# calculator6.net
KiCad netlist of a schematic drawn in EAGLE
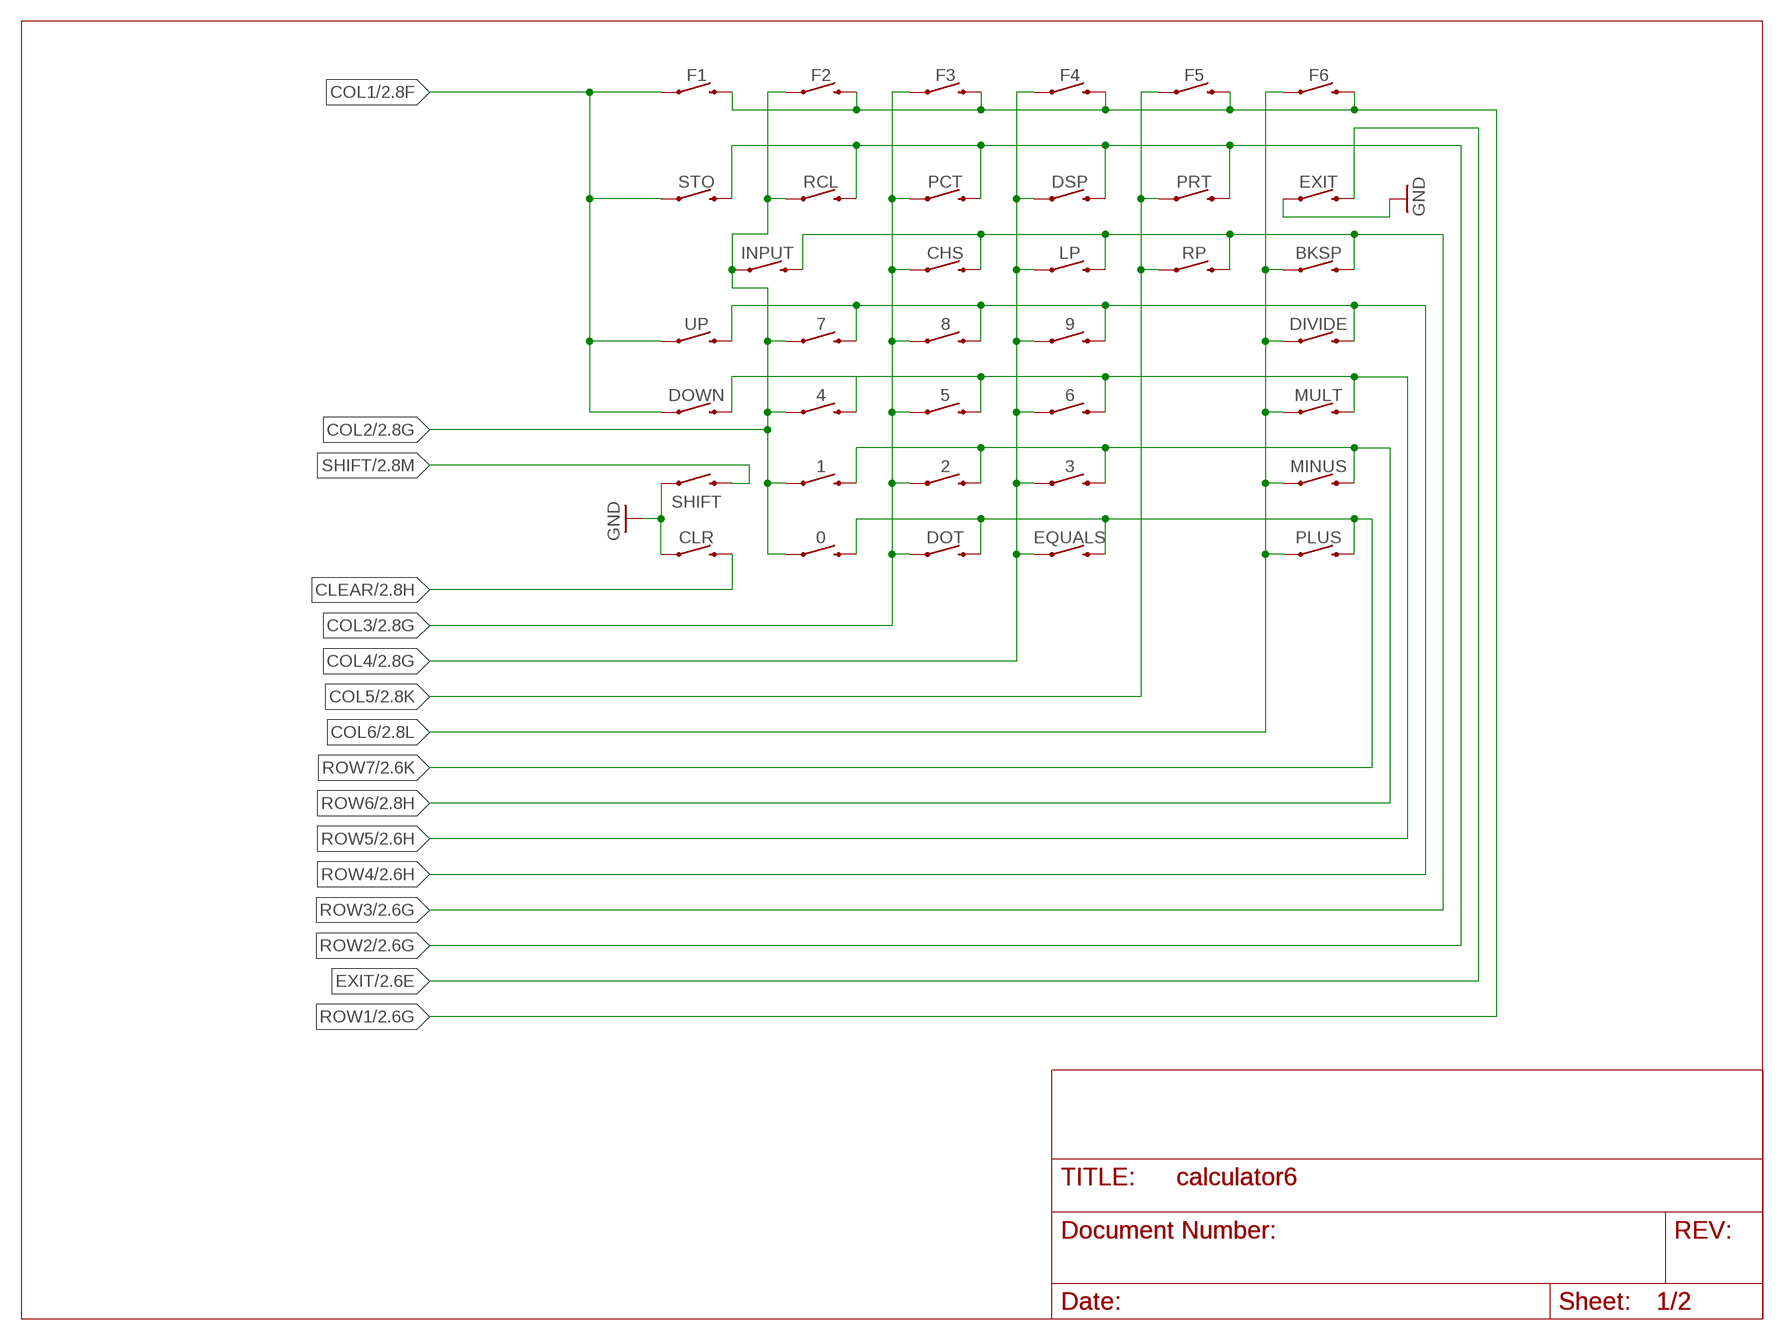
[diagram p0: schematic, sheet 1]
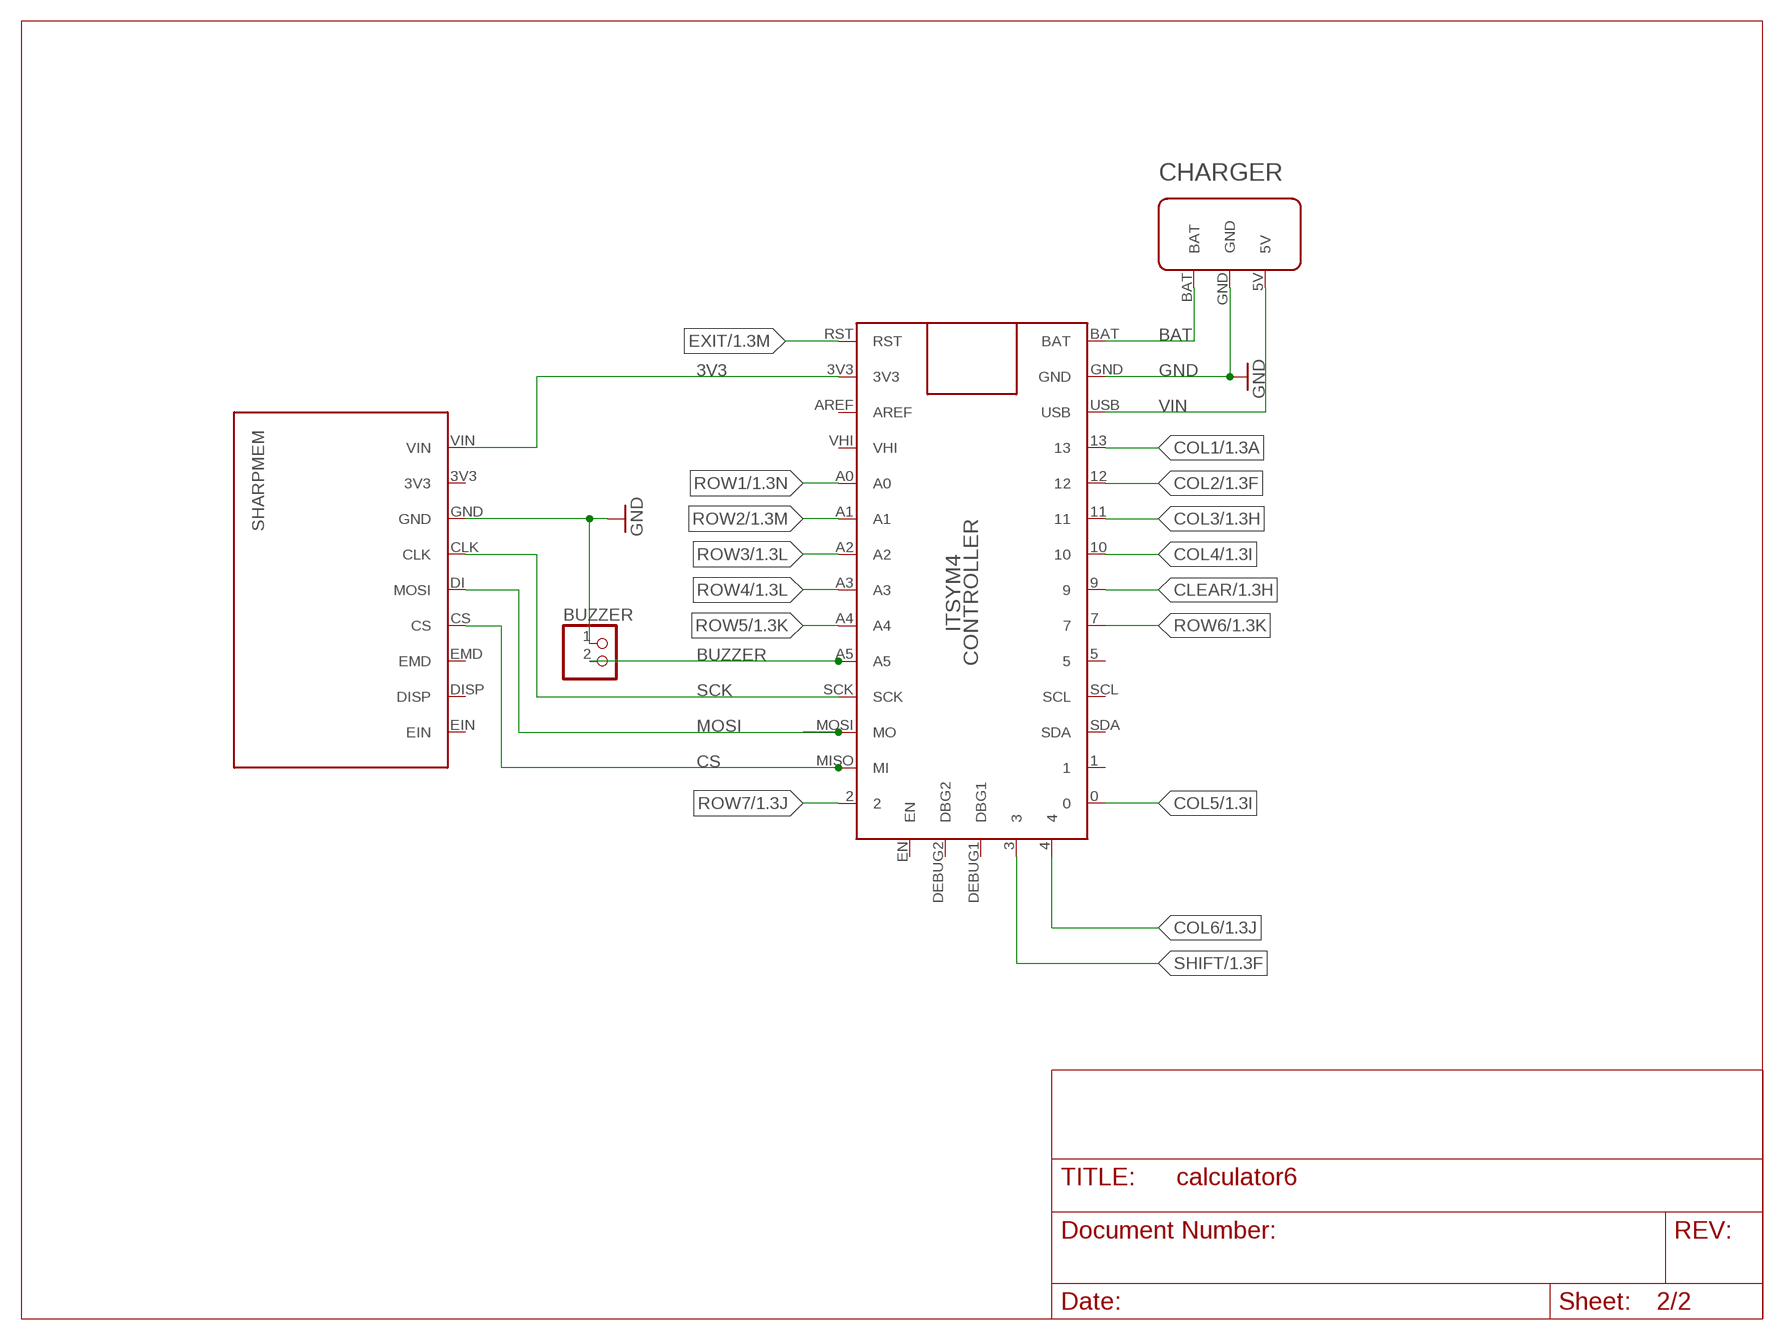
[diagram p1: schematic, sheet 2]

(export (version "E")
  (design (tool "Eeschema 10.0.6"))
  (components
    (comp (ref "0")
      (value "BUTTON")
      (footprint "eagle-import:BUTTON")
      (libsource (lib "eagle-import") (part "BUTTON"))
    )
    (comp (ref "1")
      (value "BUTTON")
      (footprint "eagle-import:BUTTON")
      (libsource (lib "eagle-import") (part "BUTTON"))
    )
    (comp (ref "2")
      (value "BUTTON")
      (footprint "eagle-import:BUTTON")
      (libsource (lib "eagle-import") (part "BUTTON"))
    )
    (comp (ref "3")
      (value "BUTTON")
      (footprint "eagle-import:BUTTON")
      (libsource (lib "eagle-import") (part "BUTTON"))
    )
    (comp (ref "4")
      (value "BUTTON")
      (footprint "eagle-import:BUTTON")
      (libsource (lib "eagle-import") (part "BUTTON"))
    )
    (comp (ref "5")
      (value "BUTTON")
      (footprint "eagle-import:BUTTON")
      (libsource (lib "eagle-import") (part "BUTTON"))
    )
    (comp (ref "6")
      (value "BUTTON")
      (footprint "eagle-import:BUTTON")
      (libsource (lib "eagle-import") (part "BUTTON"))
    )
    (comp (ref "7")
      (value "BUTTON")
      (footprint "eagle-import:BUTTON")
      (libsource (lib "eagle-import") (part "BUTTON"))
    )
    (comp (ref "8")
      (value "BUTTON")
      (footprint "eagle-import:BUTTON")
      (libsource (lib "eagle-import") (part "BUTTON"))
    )
    (comp (ref "9")
      (value "BUTTON")
      (footprint "eagle-import:BUTTON")
      (libsource (lib "eagle-import") (part "BUTTON"))
    )
    (comp (ref "BKSP")
      (value "BUTTON")
      (footprint "eagle-import:BUTTON")
      (libsource (lib "eagle-import") (part "BUTTON"))
    )
    (comp (ref "CHS")
      (value "BUTTON")
      (footprint "eagle-import:BUTTON")
      (libsource (lib "eagle-import") (part "BUTTON"))
    )
    (comp (ref "CLR")
      (value "BUTTON")
      (footprint "eagle-import:BUTTON")
      (libsource (lib "eagle-import") (part "BUTTON"))
    )
    (comp (ref "DIVIDE")
      (value "BUTTON")
      (footprint "eagle-import:BUTTON")
      (libsource (lib "eagle-import") (part "BUTTON"))
    )
    (comp (ref "DOT")
      (value "BUTTON")
      (footprint "eagle-import:BUTTON")
      (libsource (lib "eagle-import") (part "BUTTON"))
    )
    (comp (ref "DOWN")
      (value "BUTTON")
      (footprint "eagle-import:BUTTON")
      (libsource (lib "eagle-import") (part "BUTTON"))
    )
    (comp (ref "DSP")
      (value "BUTTON")
      (footprint "eagle-import:BUTTON")
      (libsource (lib "eagle-import") (part "BUTTON"))
    )
    (comp (ref "EQUALS")
      (value "BUTTON")
      (footprint "eagle-import:BUTTON")
      (libsource (lib "eagle-import") (part "BUTTON"))
    )
    (comp (ref "EXIT")
      (value "BUTTON")
      (footprint "eagle-import:BUTTON")
      (libsource (lib "eagle-import") (part "BUTTON"))
    )
    (comp (ref "F1")
      (value "BUTTON")
      (footprint "eagle-import:BUTTON")
      (libsource (lib "eagle-import") (part "BUTTON"))
    )
    (comp (ref "F2")
      (value "BUTTON")
      (footprint "eagle-import:BUTTON")
      (libsource (lib "eagle-import") (part "BUTTON"))
    )
    (comp (ref "F3")
      (value "BUTTON")
      (footprint "eagle-import:BUTTON")
      (libsource (lib "eagle-import") (part "BUTTON"))
    )
    (comp (ref "F4")
      (value "BUTTON")
      (footprint "eagle-import:BUTTON")
      (libsource (lib "eagle-import") (part "BUTTON"))
    )
    (comp (ref "F5")
      (value "BUTTON")
      (footprint "eagle-import:BUTTON")
      (libsource (lib "eagle-import") (part "BUTTON"))
    )
    (comp (ref "F6")
      (value "BUTTON")
      (footprint "eagle-import:BUTTON")
      (libsource (lib "eagle-import") (part "BUTTON"))
    )
    (comp (ref "INPUT")
      (value "BUTTON")
      (footprint "eagle-import:BUTTON")
      (libsource (lib "eagle-import") (part "BUTTON"))
    )
    (comp (ref "LP")
      (value "BUTTON")
      (footprint "eagle-import:BUTTON")
      (libsource (lib "eagle-import") (part "BUTTON"))
    )
    (comp (ref "MINUS")
      (value "BUTTON")
      (footprint "eagle-import:BUTTON")
      (libsource (lib "eagle-import") (part "BUTTON"))
    )
    (comp (ref "MULT")
      (value "BUTTON")
      (footprint "eagle-import:BUTTON")
      (libsource (lib "eagle-import") (part "BUTTON"))
    )
    (comp (ref "PCT")
      (value "BUTTON")
      (footprint "eagle-import:BUTTON")
      (libsource (lib "eagle-import") (part "BUTTON"))
    )
    (comp (ref "PLUS")
      (value "BUTTON")
      (footprint "eagle-import:BUTTON")
      (libsource (lib "eagle-import") (part "BUTTON"))
    )
    (comp (ref "PRT")
      (value "BUTTON")
      (footprint "eagle-import:BUTTON")
      (libsource (lib "eagle-import") (part "BUTTON"))
    )
    (comp (ref "RCL")
      (value "BUTTON")
      (footprint "eagle-import:BUTTON")
      (libsource (lib "eagle-import") (part "BUTTON"))
    )
    (comp (ref "RP")
      (value "BUTTON")
      (footprint "eagle-import:BUTTON")
      (libsource (lib "eagle-import") (part "BUTTON"))
    )
    (comp (ref "SHIFT")
      (value "BUTTON")
      (footprint "eagle-import:BUTTON")
      (libsource (lib "eagle-import") (part "BUTTON"))
    )
    (comp (ref "STO")
      (value "BUTTON")
      (footprint "eagle-import:BUTTON")
      (libsource (lib "eagle-import") (part "BUTTON"))
    )
    (comp (ref "UP")
      (value "BUTTON")
      (footprint "eagle-import:BUTTON")
      (libsource (lib "eagle-import") (part "BUTTON"))
    )
    (comp (ref "BUZZER")
      (value "PINHD-1X2")
      (footprint "eagle-import:1X02")
      (libsource (lib "eagle-import") (part "PINHD-1X2"))
    )
    (comp (ref "CHARGER")
      (value "LIPO_BACKPACK")
      (footprint "eagle-import:LIPO_BACKPACK")
      (libsource (lib "eagle-import") (part "LIPO_BACKPACK"))
    )
    (comp (ref "CONTROLLER")
      (value "ITSYM4")
      (footprint "eagle-import:ITSYM4")
      (libsource (lib "eagle-import") (part "ITSYM4"))
    )
    (comp (ref "SHARPMEM")
      (value "SHARPMEM")
      (footprint "eagle-import:SHARPMEM")
      (libsource (lib "eagle-import") (part "SHARPMEM"))
    )
  )
  (nets
    (net (code "1") (name "3V3") (class "Default")
      (node (ref "CONTROLLER") (pin "3V3") (pinfunction "3V3_3V3") (pintype "bidirectional"))
      (node (ref "SHARPMEM") (pin "VIN") (pinfunction "VIN_VIN") (pintype "bidirectional"))
    )
    (net (code "2") (name "BAT") (class "Default")
      (node (ref "CHARGER") (pin "BAT") (pinfunction "BAT_BAT") (pintype "bidirectional"))
      (node (ref "CONTROLLER") (pin "BAT") (pinfunction "BAT_BAT") (pintype "bidirectional"))
    )
    (net (code "3") (name "BUZZER") (class "Default")
      (node (ref "BUZZER") (pin "2") (pinfunction "2_2") (pintype "passive"))
      (node (ref "CONTROLLER") (pin "A5") (pinfunction "A5_A5") (pintype "bidirectional"))
    )
    (net (code "4") (name "CLEAR") (class "Default")
      (node (ref "CLR") (pin "3") (pinfunction "2_3") (pintype "passive"))
      (node (ref "CONTROLLER") (pin "9") (pinfunction "9_9") (pintype "bidirectional"))
    )
    (net (code "5") (name "COL1") (class "Default")
      (node (ref "CONTROLLER") (pin "13") (pinfunction "13_13") (pintype "bidirectional"))
      (node (ref "DOWN") (pin "1") (pinfunction "1_1") (pintype "passive"))
      (node (ref "F1") (pin "1") (pinfunction "1_1") (pintype "passive"))
      (node (ref "STO") (pin "1") (pinfunction "1_1") (pintype "passive"))
      (node (ref "UP") (pin "1") (pinfunction "1_1") (pintype "passive"))
    )
    (net (code "6") (name "COL2") (class "Default")
      (node (ref "0") (pin "1") (pinfunction "1_1") (pintype "passive"))
      (node (ref "1") (pin "1") (pinfunction "1_1") (pintype "passive"))
      (node (ref "4") (pin "1") (pinfunction "1_1") (pintype "passive"))
      (node (ref "7") (pin "1") (pinfunction "1_1") (pintype "passive"))
      (node (ref "CONTROLLER") (pin "12") (pinfunction "12_12") (pintype "bidirectional"))
      (node (ref "F2") (pin "1") (pinfunction "1_1") (pintype "passive"))
      (node (ref "INPUT") (pin "1") (pinfunction "1_1") (pintype "passive"))
      (node (ref "RCL") (pin "1") (pinfunction "1_1") (pintype "passive"))
    )
    (net (code "7") (name "COL3") (class "Default")
      (node (ref "2") (pin "1") (pinfunction "1_1") (pintype "passive"))
      (node (ref "5") (pin "1") (pinfunction "1_1") (pintype "passive"))
      (node (ref "8") (pin "1") (pinfunction "1_1") (pintype "passive"))
      (node (ref "CHS") (pin "1") (pinfunction "1_1") (pintype "passive"))
      (node (ref "CONTROLLER") (pin "11") (pinfunction "11_11") (pintype "bidirectional"))
      (node (ref "DOT") (pin "1") (pinfunction "1_1") (pintype "passive"))
      (node (ref "F3") (pin "1") (pinfunction "1_1") (pintype "passive"))
      (node (ref "PCT") (pin "1") (pinfunction "1_1") (pintype "passive"))
    )
    (net (code "8") (name "COL4") (class "Default")
      (node (ref "3") (pin "1") (pinfunction "1_1") (pintype "passive"))
      (node (ref "6") (pin "1") (pinfunction "1_1") (pintype "passive"))
      (node (ref "9") (pin "1") (pinfunction "1_1") (pintype "passive"))
      (node (ref "CONTROLLER") (pin "10") (pinfunction "10_10") (pintype "bidirectional"))
      (node (ref "DSP") (pin "1") (pinfunction "1_1") (pintype "passive"))
      (node (ref "EQUALS") (pin "1") (pinfunction "1_1") (pintype "passive"))
      (node (ref "F4") (pin "1") (pinfunction "1_1") (pintype "passive"))
      (node (ref "LP") (pin "1") (pinfunction "1_1") (pintype "passive"))
    )
    (net (code "9") (name "COL5") (class "Default")
      (node (ref "CONTROLLER") (pin "0") (pinfunction "0_0") (pintype "bidirectional"))
      (node (ref "F5") (pin "1") (pinfunction "1_1") (pintype "passive"))
      (node (ref "PRT") (pin "1") (pinfunction "1_1") (pintype "passive"))
      (node (ref "RP") (pin "1") (pinfunction "1_1") (pintype "passive"))
    )
    (net (code "10") (name "COL6") (class "Default")
      (node (ref "BKSP") (pin "1") (pinfunction "1_1") (pintype "passive"))
      (node (ref "CONTROLLER") (pin "4") (pinfunction "4_4") (pintype "bidirectional"))
      (node (ref "DIVIDE") (pin "1") (pinfunction "1_1") (pintype "passive"))
      (node (ref "F6") (pin "1") (pinfunction "1_1") (pintype "passive"))
      (node (ref "MINUS") (pin "1") (pinfunction "1_1") (pintype "passive"))
      (node (ref "MULT") (pin "1") (pinfunction "1_1") (pintype "passive"))
      (node (ref "PLUS") (pin "1") (pinfunction "1_1") (pintype "passive"))
    )
    (net (code "11") (name "CS") (class "Default")
      (node (ref "CONTROLLER") (pin "MISO") (pinfunction "MI_MISO") (pintype "bidirectional"))
      (node (ref "SHARPMEM") (pin "CS") (pinfunction "CS_CS") (pintype "bidirectional"))
    )
    (net (code "12") (name "EXIT") (class "Default")
      (node (ref "CONTROLLER") (pin "RST") (pinfunction "RST_RST") (pintype "bidirectional"))
      (node (ref "EXIT") (pin "3") (pinfunction "2_3") (pintype "passive"))
    )
    (net (code "13") (name "GND") (class "Default")
      (node (ref "BUZZER") (pin "1") (pinfunction "1_1") (pintype "passive"))
      (node (ref "CHARGER") (pin "GND") (pinfunction "GND_GND") (pintype "bidirectional"))
      (node (ref "CLR") (pin "1") (pinfunction "1_1") (pintype "passive"))
      (node (ref "CONTROLLER") (pin "GND") (pinfunction "GND_GND") (pintype "bidirectional"))
      (node (ref "EXIT") (pin "1") (pinfunction "1_1") (pintype "passive"))
      (node (ref "SHARPMEM") (pin "GND") (pinfunction "GND_GND") (pintype "bidirectional"))
      (node (ref "SHIFT") (pin "1") (pinfunction "1_1") (pintype "passive"))
    )
    (net (code "14") (name "MOSI") (class "Default")
      (node (ref "CONTROLLER") (pin "MOSI") (pinfunction "MO_MOSI") (pintype "bidirectional"))
      (node (ref "SHARPMEM") (pin "DI") (pinfunction "MOSI_DI") (pintype "bidirectional"))
    )
    (net (code "15") (name "ROW1") (class "Default")
      (node (ref "CONTROLLER") (pin "A0") (pinfunction "A0_A0") (pintype "bidirectional"))
      (node (ref "F1") (pin "3") (pinfunction "2_3") (pintype "passive"))
      (node (ref "F2") (pin "3") (pinfunction "2_3") (pintype "passive"))
      (node (ref "F3") (pin "3") (pinfunction "2_3") (pintype "passive"))
      (node (ref "F4") (pin "3") (pinfunction "2_3") (pintype "passive"))
      (node (ref "F5") (pin "3") (pinfunction "2_3") (pintype "passive"))
      (node (ref "F6") (pin "3") (pinfunction "2_3") (pintype "passive"))
    )
    (net (code "16") (name "ROW2") (class "Default")
      (node (ref "CONTROLLER") (pin "A1") (pinfunction "A1_A1") (pintype "bidirectional"))
      (node (ref "DSP") (pin "3") (pinfunction "2_3") (pintype "passive"))
      (node (ref "PCT") (pin "3") (pinfunction "2_3") (pintype "passive"))
      (node (ref "PRT") (pin "3") (pinfunction "2_3") (pintype "passive"))
      (node (ref "RCL") (pin "3") (pinfunction "2_3") (pintype "passive"))
      (node (ref "STO") (pin "3") (pinfunction "2_3") (pintype "passive"))
    )
    (net (code "17") (name "ROW3") (class "Default")
      (node (ref "BKSP") (pin "3") (pinfunction "2_3") (pintype "passive"))
      (node (ref "CHS") (pin "3") (pinfunction "2_3") (pintype "passive"))
      (node (ref "CONTROLLER") (pin "A2") (pinfunction "A2_A2") (pintype "bidirectional"))
      (node (ref "INPUT") (pin "3") (pinfunction "2_3") (pintype "passive"))
      (node (ref "LP") (pin "3") (pinfunction "2_3") (pintype "passive"))
      (node (ref "RP") (pin "3") (pinfunction "2_3") (pintype "passive"))
    )
    (net (code "18") (name "ROW4") (class "Default")
      (node (ref "7") (pin "3") (pinfunction "2_3") (pintype "passive"))
      (node (ref "8") (pin "3") (pinfunction "2_3") (pintype "passive"))
      (node (ref "9") (pin "3") (pinfunction "2_3") (pintype "passive"))
      (node (ref "CONTROLLER") (pin "A3") (pinfunction "A3_A3") (pintype "bidirectional"))
      (node (ref "DIVIDE") (pin "3") (pinfunction "2_3") (pintype "passive"))
      (node (ref "UP") (pin "3") (pinfunction "2_3") (pintype "passive"))
    )
    (net (code "19") (name "ROW5") (class "Default")
      (node (ref "4") (pin "3") (pinfunction "2_3") (pintype "passive"))
      (node (ref "5") (pin "3") (pinfunction "2_3") (pintype "passive"))
      (node (ref "6") (pin "3") (pinfunction "2_3") (pintype "passive"))
      (node (ref "CONTROLLER") (pin "A4") (pinfunction "A4_A4") (pintype "bidirectional"))
      (node (ref "DOWN") (pin "3") (pinfunction "2_3") (pintype "passive"))
      (node (ref "MULT") (pin "3") (pinfunction "2_3") (pintype "passive"))
    )
    (net (code "20") (name "ROW6") (class "Default")
      (node (ref "1") (pin "3") (pinfunction "2_3") (pintype "passive"))
      (node (ref "2") (pin "3") (pinfunction "2_3") (pintype "passive"))
      (node (ref "3") (pin "3") (pinfunction "2_3") (pintype "passive"))
      (node (ref "CONTROLLER") (pin "7") (pinfunction "7_7") (pintype "bidirectional"))
      (node (ref "MINUS") (pin "3") (pinfunction "2_3") (pintype "passive"))
    )
    (net (code "21") (name "ROW7") (class "Default")
      (node (ref "0") (pin "3") (pinfunction "2_3") (pintype "passive"))
      (node (ref "CONTROLLER") (pin "2") (pinfunction "2_2") (pintype "bidirectional"))
      (node (ref "DOT") (pin "3") (pinfunction "2_3") (pintype "passive"))
      (node (ref "EQUALS") (pin "3") (pinfunction "2_3") (pintype "passive"))
      (node (ref "PLUS") (pin "3") (pinfunction "2_3") (pintype "passive"))
    )
    (net (code "22") (name "SCK") (class "Default")
      (node (ref "CONTROLLER") (pin "SCK") (pinfunction "SCK_SCK") (pintype "bidirectional"))
      (node (ref "SHARPMEM") (pin "CLK") (pinfunction "CLK_CLK") (pintype "bidirectional"))
    )
    (net (code "23") (name "SHIFT") (class "Default")
      (node (ref "CONTROLLER") (pin "3") (pinfunction "3_3") (pintype "bidirectional"))
      (node (ref "SHIFT") (pin "3") (pinfunction "2_3") (pintype "passive"))
    )
    (net (code "24") (name "VIN") (class "Default")
      (node (ref "CHARGER") (pin "5V") (pinfunction "5V_5V") (pintype "bidirectional"))
      (node (ref "CONTROLLER") (pin "USB") (pinfunction "USB_USB") (pintype "bidirectional"))
    )
    (net (code "25") (name "unconnected-(CONTROLLER-DBG1-PadDEBUG1)") (class "Default")
      (node (ref "CONTROLLER") (pin "DEBUG1") (pinfunction "DBG1_DEBUG1") (pintype "bidirectional"))
    )
    (net (code "26") (name "unconnected-(CONTROLLER-DBG2-PadDEBUG2)") (class "Default")
      (node (ref "CONTROLLER") (pin "DEBUG2") (pinfunction "DBG2_DEBUG2") (pintype "bidirectional"))
    )
    (net (code "27") (name "unconnected-(CONTROLLER-Pad1)") (class "Default")
      (node (ref "CONTROLLER") (pin "1") (pinfunction "1_1") (pintype "bidirectional"))
    )
    (net (code "28") (name "unconnected-(CONTROLLER-Pad5)") (class "Default")
      (node (ref "CONTROLLER") (pin "5") (pinfunction "5_5") (pintype "bidirectional"))
    )
    (net (code "29") (name "unconnected-(CONTROLLER-PadAREF)") (class "Default")
      (node (ref "CONTROLLER") (pin "AREF") (pinfunction "AREF_AREF") (pintype "bidirectional"))
    )
    (net (code "30") (name "unconnected-(CONTROLLER-PadEN)") (class "Default")
      (node (ref "CONTROLLER") (pin "EN") (pinfunction "EN_EN") (pintype "bidirectional"))
    )
    (net (code "31") (name "unconnected-(CONTROLLER-PadSCL)") (class "Default")
      (node (ref "CONTROLLER") (pin "SCL") (pinfunction "SCL_SCL") (pintype "bidirectional"))
    )
    (net (code "32") (name "unconnected-(CONTROLLER-PadSDA)") (class "Default")
      (node (ref "CONTROLLER") (pin "SDA") (pinfunction "SDA_SDA") (pintype "bidirectional"))
    )
    (net (code "33") (name "unconnected-(CONTROLLER-PadVHI)") (class "Default")
      (node (ref "CONTROLLER") (pin "VHI") (pinfunction "VHI_VHI") (pintype "bidirectional"))
    )
    (net (code "34") (name "unconnected-(SHARPMEM-Pad3V3)") (class "Default")
      (node (ref "SHARPMEM") (pin "3V3") (pinfunction "3V3_3V3") (pintype "bidirectional"))
    )
    (net (code "35") (name "unconnected-(SHARPMEM-PadDISP)") (class "Default")
      (node (ref "SHARPMEM") (pin "DISP") (pinfunction "DISP_DISP") (pintype "bidirectional"))
    )
    (net (code "36") (name "unconnected-(SHARPMEM-PadEIN)") (class "Default")
      (node (ref "SHARPMEM") (pin "EIN") (pinfunction "EIN_EIN") (pintype "bidirectional"))
    )
    (net (code "37") (name "unconnected-(SHARPMEM-PadEMD)") (class "Default")
      (node (ref "SHARPMEM") (pin "EMD") (pinfunction "EMD_EMD") (pintype "bidirectional"))
    )
  )
)
